# POWER.net
KiCad netlist of a schematic drawn in Altium Designer
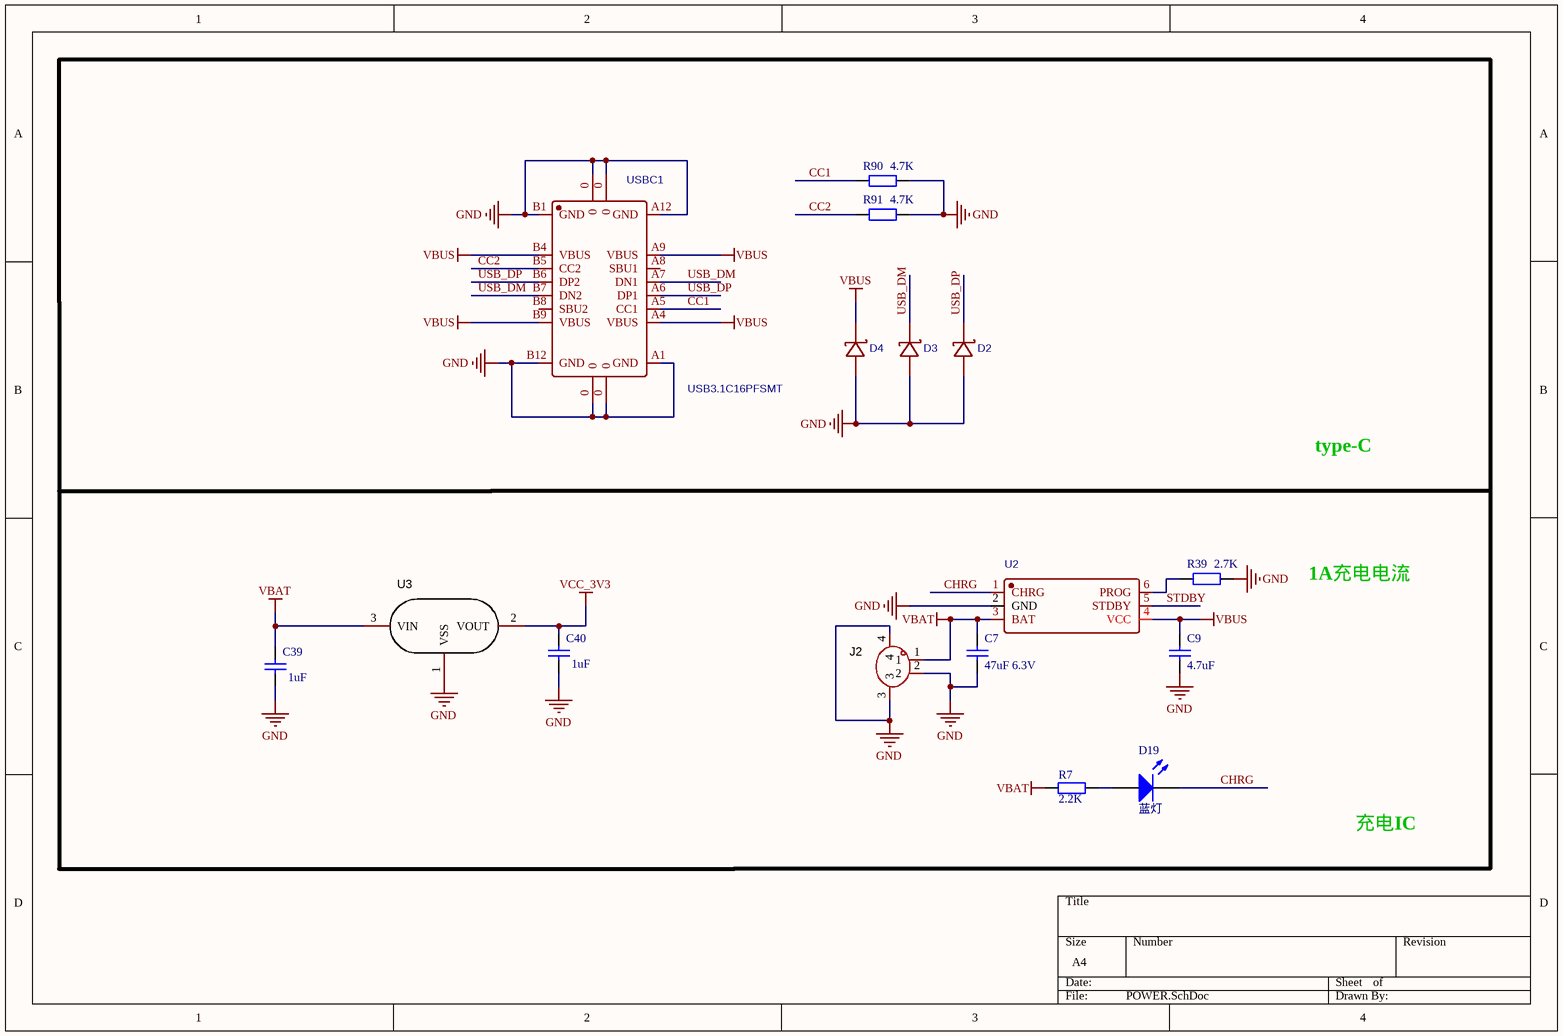
[diagram p0: POWER.SchDoc]

(export (version "E")
  (design (tool "Eeschema 10.0.6"))
  (components
    (comp (ref "C7")
      (value "47uF 6.3V")
      (footprint "0805C")
      (description "Capacitor")
      (fields (field (name "PUBLISHER") "Altium Limited"))
      (libsource (lib "Miscellaneous Devices") (part "Cap"))
    )
    (comp (ref "C9")
      (value "4.7uF")
      (footprint "0402C")
      (description "Capacitor")
      (fields (field (name "PUBLISHER") "Altium Limited"))
      (libsource (lib "Miscellaneous Devices") (part "Cap"))
    )
    (comp (ref "C39")
      (value "1uF")
      (footprint "0402C")
      (description "Capacitor")
      (fields (field (name "PUBLISHER") "Altium Limited"))
      (libsource (lib "Miscellaneous Devices") (part "Cap"))
    )
    (comp (ref "C40")
      (value "1uF")
      (footprint "0402C")
      (description "Capacitor")
      (fields (field (name "PUBLISHER") "Altium Limited"))
      (libsource (lib "Miscellaneous Devices") (part "Cap"))
    )
    (comp (ref "D2")
      (value "LESD8LL5.0T5G")
      (footprint "SOD-882_L1.0-W0.6-RD")
      (description "ESD")
      (fields (field (name "BOM_SUPPLIER PART") "C172423") (field (name "CONTRIBUTOR") "LCSC"))
      (libsource (lib "altium-import") (part "root_3_LESD8LL5.0T5G_"))
    )
    (comp (ref "D3")
      (value "LESD8LL5.0T5G")
      (footprint "SOD-882_L1.0-W0.6-RD")
      (description "ESD")
      (fields (field (name "BOM_SUPPLIER PART") "C172423") (field (name "CONTRIBUTOR") "LCSC"))
      (libsource (lib "altium-import") (part "root_3_LESD8LL5.0T5G_"))
    )
    (comp (ref "D4")
      (value "LESD8LL5.0T5G")
      (footprint "SOD-882_L1.0-W0.6-RD")
      (description "ESD")
      (fields (field (name "BOM_SUPPLIER PART") "C172423") (field (name "CONTRIBUTOR") "LCSC"))
      (libsource (lib "altium-import") (part "root_3_LESD8LL5.0T5G_"))
    )
    (comp (ref "D19")
      (value "蓝灯")
      (footprint "LED-0603_RD")
      (description "Typical INFRARED GaAs LED")
      (fields (field (name "Comment") "XL-2012UBC") (field (name "PUBLISHER") "Altium Limited"))
      (libsource (lib "Miscellaneous Devices") (part "LED0"))
    )
    (comp (ref "J2")
      (value "WAFER-MX1.25-2PWB")
      (footprint "CONN-SMD_2P-P1.25_XUNPU_WAFER-MX1.25-2PWB")
      (description "WAFER")
      (fields (field (name "MANUFACTURER") "XUNPU(讯普)"))
      (libsource (lib "altium-import") (part "root_0_mirrored_WAFER-MX1.25-2PWB_"))
    )
    (comp (ref "R7")
      (value "2.2K")
      (footprint "0402R")
      (description "Resistor")
      (fields (field (name "PUBLISHER") "Altium Limited"))
      (libsource (lib "") (part "Res2_1"))
    )
    (comp (ref "R39")
      (value "2.7K")
      (footprint "0402R")
      (description "Resistor")
      (fields (field (name "PUBLISHER") "Altium Limited"))
      (libsource (lib "Miscellaneous Devices") (part "Res2"))
    )
    (comp (ref "R90")
      (value "4.7K")
      (footprint "0402R")
      (description "Resistor")
      (fields (field (name "PUBLISHER") "Altium Limited"))
      (libsource (lib "Miscellaneous Devices") (part "Res2"))
    )
    (comp (ref "R91")
      (value "4.7K")
      (footprint "0402R")
      (description "Resistor")
      (fields (field (name "PUBLISHER") "Altium Limited"))
      (libsource (lib "Miscellaneous Devices") (part "Res2"))
    )
    (comp (ref "U2")
      (value "ME4055AM6G-N")
      (footprint "SOT-23-6PIN")
      (description "充电IC")
      (fields (field (name "BOM_SUPPLIER PART") "C82121") (field (name "CONTRIBUTOR") "LCSC"))
      (libsource (lib "altium-import") (part "root_0_HX4057A_"))
    )
    (comp (ref "U3")
      (value "XC6206P332MR")
      (footprint "SOT-23")
      (description "LDO")
      (fields (field (name "MANUFACTURER") "MICRONE(南京微盟)") (field (name "MANUFACTURER PART") "ME6203A50M3G"))
      (libsource (lib "altium-import") (part "root_0_ME6203A50M3G_"))
    )
    (comp (ref "USBC1")
      (value "USB3.1C16PFSMT")
      (footprint "USB-C-SMD_TYPE-C-USB-17")
      (description "USBC")
      (fields (field (name "BOM_SUPPLIER PART") "C167321") (field (name "CONTRIBUTOR") "LCSC"))
      (libsource (lib "altium-import") (part "root_0_USB3.1C16PFSMT_"))
    )
  )
  (nets
    (net (code "1") (name "/CC1") (class "Default")
      (node (ref "R90") (pin "1") (pinfunction "1_1") (pintype "passive"))
      (node (ref "USBC1") (pin "A5") (pinfunction "CC1_A5") (pintype "passive"))
    )
    (net (code "2") (name "/CC2") (class "Default")
      (node (ref "R91") (pin "1") (pinfunction "1_1") (pintype "passive"))
      (node (ref "USBC1") (pin "B5") (pinfunction "CC2_B5") (pintype "passive"))
    )
    (net (code "3") (name "/CHRG") (class "Default")
      (node (ref "D19") (pin "2") (pinfunction "K_2") (pintype "passive"))
      (node (ref "U2") (pin "1") (pinfunction "CHRG_1") (pintype "passive"))
    )
    (net (code "4") (name "/STDBY") (class "Default")
      (node (ref "U2") (pin "5") (pinfunction "STDBY_5") (pintype "passive"))
    )
    (net (code "5") (name "/USB_DM") (class "Default")
      (node (ref "D3") (pin "1") (pinfunction "C_1") (pintype "passive"))
      (node (ref "USBC1") (pin "A7") (pinfunction "DN1_A7") (pintype "passive"))
      (node (ref "USBC1") (pin "B7") (pinfunction "DN2_B7") (pintype "passive"))
    )
    (net (code "6") (name "/USB_DP") (class "Default")
      (node (ref "D2") (pin "1") (pinfunction "C_1") (pintype "passive"))
      (node (ref "USBC1") (pin "A6") (pinfunction "DP1_A6") (pintype "passive"))
      (node (ref "USBC1") (pin "B6") (pinfunction "DP2_B6") (pintype "passive"))
    )
    (net (code "7") (name "GND") (class "Default")
      (node (ref "C39") (pin "1") (pinfunction "1_1") (pintype "passive"))
      (node (ref "C40") (pin "1") (pinfunction "1_1") (pintype "passive"))
      (node (ref "C7") (pin "1") (pinfunction "1_1") (pintype "passive"))
      (node (ref "C9") (pin "1") (pinfunction "1_1") (pintype "passive"))
      (node (ref "D2") (pin "2") (pinfunction "A_2") (pintype "passive"))
      (node (ref "D3") (pin "2") (pinfunction "A_2") (pintype "passive"))
      (node (ref "D4") (pin "2") (pinfunction "A_2") (pintype "passive"))
      (node (ref "J2") (pin "2") (pinfunction "2_2") (pintype "passive"))
      (node (ref "J2") (pin "3") (pinfunction "3_3") (pintype "passive"))
      (node (ref "J2") (pin "4") (pinfunction "4_4") (pintype "passive"))
      (node (ref "R39") (pin "2") (pinfunction "2_2") (pintype "passive"))
      (node (ref "R90") (pin "2") (pinfunction "2_2") (pintype "passive"))
      (node (ref "R91") (pin "2") (pinfunction "2_2") (pintype "passive"))
      (node (ref "U2") (pin "2") (pinfunction "GND_2") (pintype "passive"))
      (node (ref "U3") (pin "1") (pinfunction "VSS_1") (pintype "passive"))
      (node (ref "USBC1") (pin "0") (pinfunction "0_0") (pintype "passive"))
      (node (ref "USBC1") (pin "A1") (pinfunction "GND_A1") (pintype "passive"))
      (node (ref "USBC1") (pin "A12") (pinfunction "GND_A12") (pintype "passive"))
      (node (ref "USBC1") (pin "B1") (pinfunction "GND_B1") (pintype "passive"))
      (node (ref "USBC1") (pin "B12") (pinfunction "GND_B12") (pintype "passive"))
    )
    (net (code "8") (name "Net-(D19-A)") (class "Default")
      (node (ref "D19") (pin "1") (pinfunction "A_1") (pintype "passive"))
      (node (ref "R7") (pin "1") (pinfunction "1_1") (pintype "passive"))
    )
    (net (code "9") (name "Net-(U2-PROG)") (class "Default")
      (node (ref "R39") (pin "1") (pinfunction "1_1") (pintype "passive"))
      (node (ref "U2") (pin "6") (pinfunction "PROG_6") (pintype "passive"))
    )
    (net (code "10") (name "VBAT") (class "Default")
      (node (ref "C39") (pin "2") (pinfunction "2_2") (pintype "passive"))
      (node (ref "C7") (pin "2") (pinfunction "2_2") (pintype "passive"))
      (node (ref "J2") (pin "1") (pinfunction "1_1") (pintype "passive"))
      (node (ref "R7") (pin "2") (pinfunction "2_2") (pintype "passive"))
      (node (ref "U2") (pin "3") (pinfunction "BAT_3") (pintype "passive"))
      (node (ref "U3") (pin "3") (pinfunction "VIN_3") (pintype "passive"))
    )
    (net (code "11") (name "VBUS") (class "Default")
      (node (ref "C9") (pin "2") (pinfunction "2_2") (pintype "passive"))
      (node (ref "D4") (pin "1") (pinfunction "C_1") (pintype "passive"))
      (node (ref "U2") (pin "4") (pinfunction "VCC_4") (pintype "passive"))
      (node (ref "USBC1") (pin "A4") (pinfunction "VBUS_A4") (pintype "passive"))
      (node (ref "USBC1") (pin "A9") (pinfunction "VBUS_A9") (pintype "passive"))
      (node (ref "USBC1") (pin "B4") (pinfunction "VBUS_B4") (pintype "passive"))
      (node (ref "USBC1") (pin "B9") (pinfunction "VBUS_B9") (pintype "passive"))
    )
    (net (code "12") (name "VCC_3V3") (class "Default")
      (node (ref "C40") (pin "2") (pinfunction "2_2") (pintype "passive"))
      (node (ref "U3") (pin "2") (pinfunction "VOUT_2") (pintype "passive"))
    )
    (net (code "13") (name "unconnected-(USBC1-SBU1-PadA8)") (class "Default")
      (node (ref "USBC1") (pin "A8") (pinfunction "SBU1_A8") (pintype "passive"))
    )
    (net (code "14") (name "unconnected-(USBC1-SBU2-PadB8)") (class "Default")
      (node (ref "USBC1") (pin "B8") (pinfunction "SBU2_B8") (pintype "passive"))
    )
  )
)
